# FlightPCB.net
KiCad netlist of a schematic drawn in EAGLE
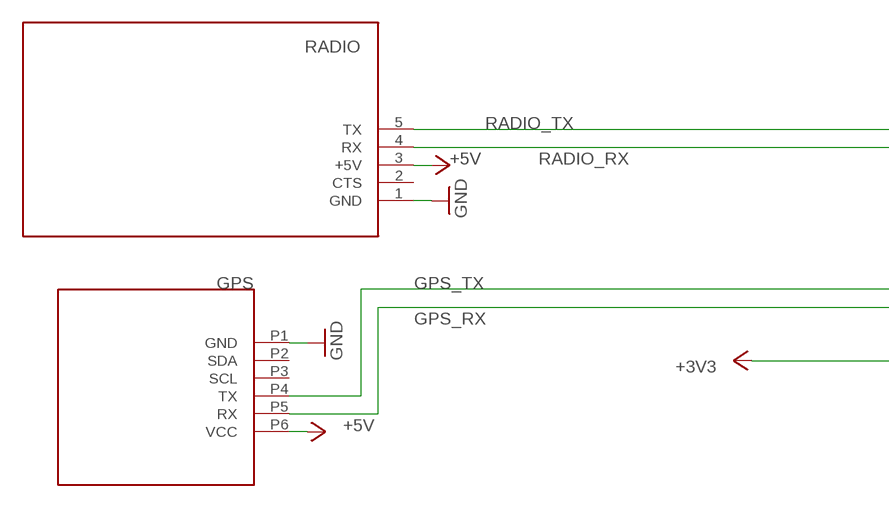
[diagram p0: schematic, sheet 1, part 1 of 2]
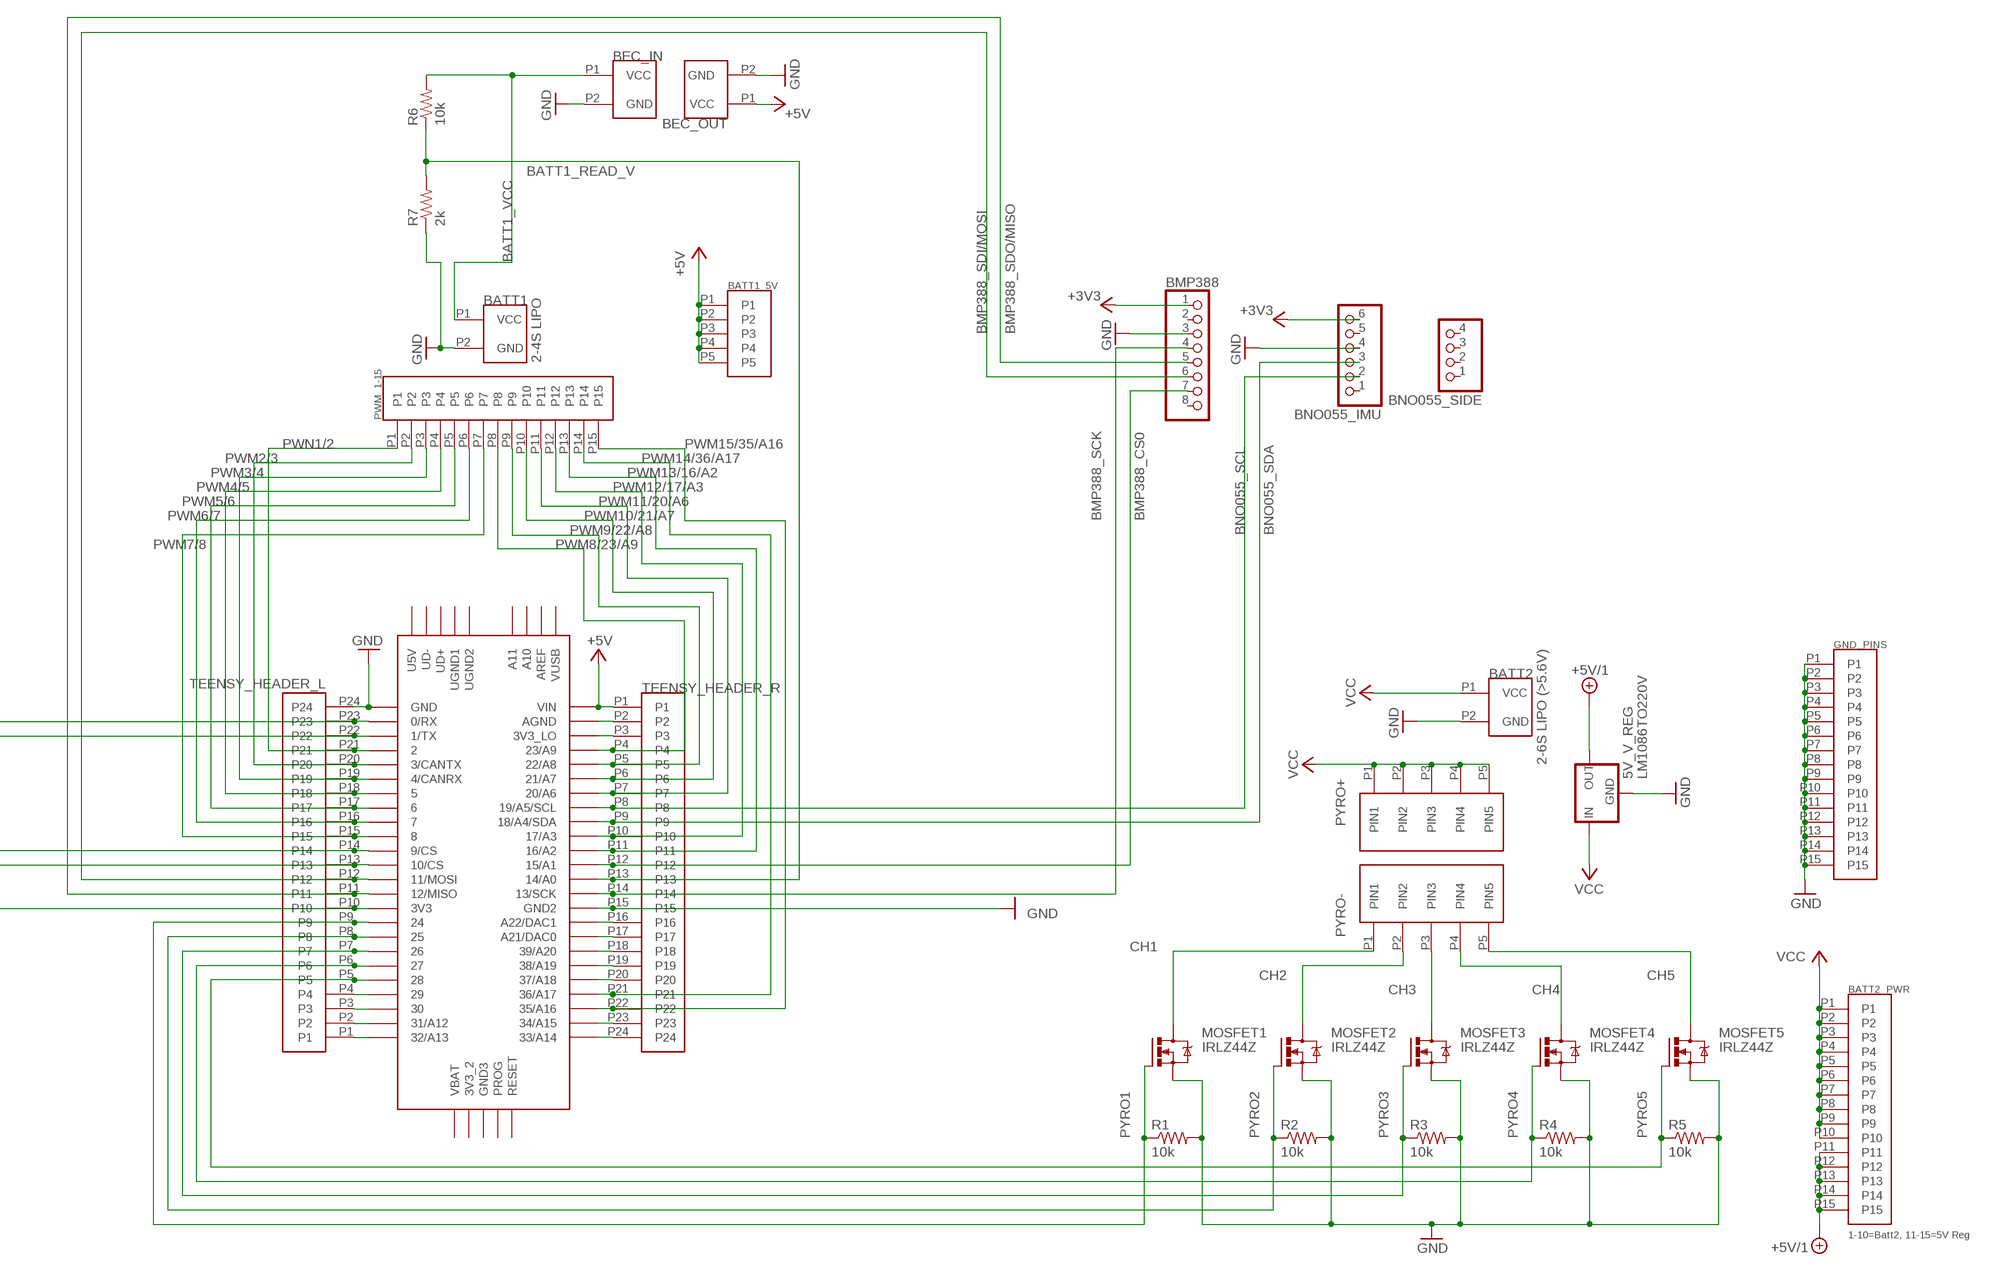
[diagram p1: schematic, sheet 1, part 2 of 2]

(export (version "E")
  (design (tool "Eeschema 10.0.6"))
  (components
    (comp (ref "5V_V_REG")
      (value "LM1086TO220V")
      (footprint "eagle-import:TO220S")
      (libsource (lib "eagle-import") (part "LM1086TO220V"))
    )
    (comp (ref "BATT1")
      (value "2-4S LIPO")
      (footprint "eagle-import:TERMINAL_BLOCK_2_PIN_5MM")
      (libsource (lib "eagle-import") (part "TERMINAL_BLOCK_2_PIN_5MM"))
    )
    (comp (ref "BATT1_5V")
      (value "PIN_HEADER_5")
      (footprint "eagle-import:PIN_HEADER_5")
      (libsource (lib "eagle-import") (part "PIN_HEADER_5"))
    )
    (comp (ref "BATT2")
      (value "2-6S LIPO (>5.6V)")
      (footprint "eagle-import:TERMINAL_BLOCK_2_PIN_5MM")
      (libsource (lib "eagle-import") (part "TERMINAL_BLOCK_2_PIN_5MM"))
    )
    (comp (ref "BATT2_PWR")
      (value "1-10=Batt2, 11-15=5V Reg")
      (footprint "eagle-import:PIN_HEADER_15")
      (libsource (lib "eagle-import") (part "PIN_HEADER_15"))
    )
    (comp (ref "BEC_IN")
      (value "TERMINAL_BLOCK_2_PIN_5MM")
      (footprint "eagle-import:TERMINAL_BLOCK_2_PIN_5MM")
      (libsource (lib "eagle-import") (part "TERMINAL_BLOCK_2_PIN_5MM"))
    )
    (comp (ref "BEC_OUT")
      (value "TERMINAL_BLOCK_2_PIN_5MM")
      (footprint "eagle-import:TERMINAL_BLOCK_2_PIN_5MM")
      (libsource (lib "eagle-import") (part "TERMINAL_BLOCK_2_PIN_5MM"))
    )
    (comp (ref "BMP388")
      (value "MICROBUILDER_HEADER-1X8ROUND")
      (footprint "eagle-import:MICROBUILDER_1X08_ROUND")
      (libsource (lib "eagle-import") (part "MICROBUILDER_HEADER-1X8ROUND"))
    )
    (comp (ref "BNO055_IMU")
      (value "MICROBUILDER_HEADER-1X6ROUND")
      (footprint "eagle-import:MICROBUILDER_1X06_ROUND")
      (libsource (lib "eagle-import") (part "MICROBUILDER_HEADER-1X6ROUND"))
    )
    (comp (ref "BNO055_SIDE")
      (value "MICROBUILDER_HEADER-1X4ROUND")
      (footprint "eagle-import:MICROBUILDER_1X04_ROUND")
      (libsource (lib "eagle-import") (part "MICROBUILDER_HEADER-1X4ROUND"))
    )
    (comp (ref "FLIGHT_COMPUTER")
      (value "TEENSY_3.5/3.6")
      (footprint "eagle-import:TEENSY_3.5_3.6")
      (libsource (lib "eagle-import") (part "TEENSY_3.5/3.6"))
    )
    (comp (ref "GND_PINS")
      (value "PIN_HEADER_15")
      (footprint "eagle-import:PIN_HEADER_15")
      (libsource (lib "eagle-import") (part "PIN_HEADER_15"))
    )
    (comp (ref "GPS")
      (value "NEO_M8N_GPS_BREAKOUT")
      (footprint "eagle-import:NEO_M8N_GPS_BREAKOUT")
      (libsource (lib "eagle-import") (part "NEO_M8N_GPS_BREAKOUT"))
    )
    (comp (ref "MOSFET1")
      (value "IRLZ44Z")
      (footprint "eagle-import:TO220BH_SIMPLE")
      (libsource (lib "eagle-import") (part "IRLZ44Z"))
    )
    (comp (ref "MOSFET2")
      (value "IRLZ44Z")
      (footprint "eagle-import:TO220BH_SIMPLE")
      (libsource (lib "eagle-import") (part "IRLZ44Z"))
    )
    (comp (ref "MOSFET3")
      (value "IRLZ44Z")
      (footprint "eagle-import:TO220BH_SIMPLE")
      (libsource (lib "eagle-import") (part "IRLZ44Z"))
    )
    (comp (ref "MOSFET4")
      (value "IRLZ44Z")
      (footprint "eagle-import:TO220BH_SIMPLE")
      (libsource (lib "eagle-import") (part "IRLZ44Z"))
    )
    (comp (ref "MOSFET5")
      (value "IRLZ44Z")
      (footprint "eagle-import:TO220BH_SIMPLE")
      (libsource (lib "eagle-import") (part "IRLZ44Z"))
    )
    (comp (ref "PWM_1-15")
      (value "PIN_HEADER_15")
      (footprint "eagle-import:PIN_HEADER_15")
      (libsource (lib "eagle-import") (part "PIN_HEADER_15"))
    )
    (comp (ref "PYRO+")
      (value "TERMINAL_BLOCK_5_PIN_5MM")
      (footprint "eagle-import:TERMINAL_BLOCK_5_PIN_5MM")
      (libsource (lib "eagle-import") (part "TERMINAL_BLOCK_5_PIN_5MM"))
    )
    (comp (ref "PYRO-")
      (value "TERMINAL_BLOCK_5_PIN_5MM")
      (footprint "eagle-import:TERMINAL_BLOCK_5_PIN_5MM")
      (libsource (lib "eagle-import") (part "TERMINAL_BLOCK_5_PIN_5MM"))
    )
    (comp (ref "R1")
      (value "10k")
      (footprint "eagle-import:0204_7")
      (libsource (lib "eagle-import") (part "R-US_0204/7"))
    )
    (comp (ref "R2")
      (value "10k")
      (footprint "eagle-import:0204_7")
      (libsource (lib "eagle-import") (part "R-US_0204/7"))
    )
    (comp (ref "R3")
      (value "10k")
      (footprint "eagle-import:0204_7")
      (libsource (lib "eagle-import") (part "R-US_0204/7"))
    )
    (comp (ref "R4")
      (value "10k")
      (footprint "eagle-import:0204_7")
      (libsource (lib "eagle-import") (part "R-US_0204/7"))
    )
    (comp (ref "R5")
      (value "10k")
      (footprint "eagle-import:0204_7")
      (libsource (lib "eagle-import") (part "R-US_0204/7"))
    )
    (comp (ref "R6")
      (value "10k")
      (footprint "eagle-import:0204_7")
      (libsource (lib "eagle-import") (part "R-US_0204/7"))
    )
    (comp (ref "R7")
      (value "2k")
      (footprint "eagle-import:0204_7")
      (libsource (lib "eagle-import") (part "R-US_0204/7"))
    )
    (comp (ref "RADIO")
      (value "RFD900")
      (footprint "eagle-import:RFD900")
      (libsource (lib "eagle-import") (part "RFD900"))
    )
    (comp (ref "TEENSY_HEADER_L")
      (value "PIN_HEADER_24_TEENSY_RAIL")
      (footprint "eagle-import:PIN_HEADER_24_TEENSY_RAIL")
      (libsource (lib "eagle-import") (part "PIN_HEADER_24_TEENSY_RAIL"))
    )
    (comp (ref "TEENSY_HEADER_R")
      (value "PIN_HEADER_24_TEENSY_RAIL")
      (footprint "eagle-import:PIN_HEADER_24_TEENSY_RAIL")
      (libsource (lib "eagle-import") (part "PIN_HEADER_24_TEENSY_RAIL"))
    )
  )
  (nets
    (net (code "1") (name "+3V3") (class "Default")
      (node (ref "BMP388") (pin "1") (pinfunction "1_1") (pintype "passive"))
      (node (ref "BNO055_IMU") (pin "6") (pinfunction "6_6") (pintype "passive"))
      (node (ref "FLIGHT_COMPUTER") (pin "3V3") (pinfunction "3V3_3V3") (pintype "bidirectional"))
      (node (ref "TEENSY_HEADER_L") (pin "P10") (pinfunction "P10_P10") (pintype "bidirectional"))
    )
    (net (code "2") (name "+5V") (class "Default")
      (node (ref "BATT1_5V") (pin "P1") (pinfunction "P1_P1") (pintype "bidirectional"))
      (node (ref "BATT1_5V") (pin "P2") (pinfunction "P2_P2") (pintype "bidirectional"))
      (node (ref "BATT1_5V") (pin "P3") (pinfunction "P3_P3") (pintype "bidirectional"))
      (node (ref "BATT1_5V") (pin "P4") (pinfunction "P4_P4") (pintype "bidirectional"))
      (node (ref "BATT1_5V") (pin "P5") (pinfunction "P5_P5") (pintype "bidirectional"))
      (node (ref "BEC_OUT") (pin "P1") (pinfunction "VCC_P1") (pintype "power_in"))
      (node (ref "FLIGHT_COMPUTER") (pin "VIN") (pinfunction "VIN_VIN") (pintype "bidirectional"))
      (node (ref "GPS") (pin "P6") (pinfunction "VCC_P6") (pintype "power_in"))
      (node (ref "RADIO") (pin "3") (pinfunction "+5V_3") (pintype "power_in"))
      (node (ref "TEENSY_HEADER_R") (pin "P1") (pinfunction "P1_P1") (pintype "bidirectional"))
    )
    (net (code "3") (name "+5V{slash}1") (class "Default")
      (node (ref "5V_V_REG") (pin "2") (pinfunction "OUT_2") (pintype "passive"))
      (node (ref "BATT2_PWR") (pin "P11") (pinfunction "P11_P11") (pintype "bidirectional"))
      (node (ref "BATT2_PWR") (pin "P12") (pinfunction "P12_P12") (pintype "bidirectional"))
      (node (ref "BATT2_PWR") (pin "P13") (pinfunction "P13_P13") (pintype "bidirectional"))
      (node (ref "BATT2_PWR") (pin "P14") (pinfunction "P14_P14") (pintype "bidirectional"))
      (node (ref "BATT2_PWR") (pin "P15") (pinfunction "P15_P15") (pintype "bidirectional"))
    )
    (net (code "4") (name "/BATT1_READ_V") (class "Default")
      (node (ref "FLIGHT_COMPUTER") (pin "14/A0") (pinfunction "14/A0_14/A0") (pintype "bidirectional"))
      (node (ref "R6") (pin "1") (pinfunction "1_1") (pintype "passive"))
      (node (ref "R7") (pin "2") (pinfunction "2_2") (pintype "passive"))
      (node (ref "TEENSY_HEADER_R") (pin "P13") (pinfunction "P13_P13") (pintype "bidirectional"))
    )
    (net (code "5") (name "/BATT1_VCC") (class "Default")
      (node (ref "BATT1") (pin "P1") (pinfunction "VCC_P1") (pintype "power_in"))
      (node (ref "BEC_IN") (pin "P1") (pinfunction "VCC_P1") (pintype "power_in"))
      (node (ref "R6") (pin "2") (pinfunction "2_2") (pintype "passive"))
    )
    (net (code "6") (name "/BMP388_CS0") (class "Default")
      (node (ref "BMP388") (pin "7") (pinfunction "7_7") (pintype "passive"))
      (node (ref "FLIGHT_COMPUTER") (pin "15/A1") (pinfunction "15/A1_15/A1") (pintype "bidirectional"))
      (node (ref "TEENSY_HEADER_R") (pin "P12") (pinfunction "P12_P12") (pintype "bidirectional"))
    )
    (net (code "7") (name "/BMP388_SCK") (class "Default")
      (node (ref "BMP388") (pin "4") (pinfunction "4_4") (pintype "passive"))
      (node (ref "FLIGHT_COMPUTER") (pin "13/SCK") (pinfunction "13/SCK_13/SCK") (pintype "bidirectional"))
      (node (ref "TEENSY_HEADER_R") (pin "P14") (pinfunction "P14_P14") (pintype "bidirectional"))
    )
    (net (code "8") (name "/BMP388_SDI{slash}MOSI") (class "Default")
      (node (ref "BMP388") (pin "6") (pinfunction "6_6") (pintype "passive"))
      (node (ref "FLIGHT_COMPUTER") (pin "11/MOSI") (pinfunction "11/MOSI_11/MOSI") (pintype "bidirectional"))
      (node (ref "TEENSY_HEADER_L") (pin "P12") (pinfunction "P12_P12") (pintype "bidirectional"))
    )
    (net (code "9") (name "/BMP388_SDO{slash}MISO") (class "Default")
      (node (ref "BMP388") (pin "5") (pinfunction "5_5") (pintype "passive"))
      (node (ref "FLIGHT_COMPUTER") (pin "12/MISO") (pinfunction "12/MISO_12/MISO") (pintype "bidirectional"))
      (node (ref "TEENSY_HEADER_L") (pin "P11") (pinfunction "P11_P11") (pintype "bidirectional"))
    )
    (net (code "10") (name "/BNO055_SCL") (class "Default")
      (node (ref "BNO055_IMU") (pin "2") (pinfunction "2_2") (pintype "passive"))
      (node (ref "FLIGHT_COMPUTER") (pin "19/A5/SCL") (pinfunction "19/A5/SCL_19/A5/SCL") (pintype "bidirectional"))
      (node (ref "TEENSY_HEADER_R") (pin "P8") (pinfunction "P8_P8") (pintype "bidirectional"))
    )
    (net (code "11") (name "/BNO055_SDA") (class "Default")
      (node (ref "BNO055_IMU") (pin "3") (pinfunction "3_3") (pintype "passive"))
      (node (ref "FLIGHT_COMPUTER") (pin "18/A4/SDA") (pinfunction "18/A4/SDA_18/A4/SDA") (pintype "bidirectional"))
      (node (ref "TEENSY_HEADER_R") (pin "P9") (pinfunction "P9_P9") (pintype "bidirectional"))
    )
    (net (code "12") (name "/CH1") (class "Default")
      (node (ref "MOSFET1") (pin "D") (pinfunction "D_D") (pintype "passive"))
      (node (ref "PYRO-") (pin "P1") (pinfunction "PIN1_P1") (pintype "bidirectional"))
    )
    (net (code "13") (name "/CH2") (class "Default")
      (node (ref "MOSFET2") (pin "D") (pinfunction "D_D") (pintype "passive"))
      (node (ref "PYRO-") (pin "P2") (pinfunction "PIN2_P2") (pintype "bidirectional"))
    )
    (net (code "14") (name "/CH3") (class "Default")
      (node (ref "MOSFET3") (pin "D") (pinfunction "D_D") (pintype "passive"))
      (node (ref "PYRO-") (pin "P3") (pinfunction "PIN3_P3") (pintype "bidirectional"))
    )
    (net (code "15") (name "/CH4") (class "Default")
      (node (ref "MOSFET4") (pin "D") (pinfunction "D_D") (pintype "passive"))
      (node (ref "PYRO-") (pin "P4") (pinfunction "PIN4_P4") (pintype "bidirectional"))
    )
    (net (code "16") (name "/CH5") (class "Default")
      (node (ref "MOSFET5") (pin "D") (pinfunction "D_D") (pintype "passive"))
      (node (ref "PYRO-") (pin "P5") (pinfunction "PIN5_P5") (pintype "bidirectional"))
    )
    (net (code "17") (name "/GPS_RX") (class "Default")
      (node (ref "FLIGHT_COMPUTER") (pin "10/CS") (pinfunction "10/CS_10/CS") (pintype "bidirectional"))
      (node (ref "GPS") (pin "P5") (pinfunction "RX_P5") (pintype "input"))
      (node (ref "TEENSY_HEADER_L") (pin "P13") (pinfunction "P13_P13") (pintype "bidirectional"))
    )
    (net (code "18") (name "/GPS_TX") (class "Default")
      (node (ref "FLIGHT_COMPUTER") (pin "9/CS") (pinfunction "9/CS_9/CS") (pintype "bidirectional"))
      (node (ref "GPS") (pin "P4") (pinfunction "TX_P4") (pintype "output"))
      (node (ref "TEENSY_HEADER_L") (pin "P14") (pinfunction "P14_P14") (pintype "bidirectional"))
    )
    (net (code "19") (name "/PWM2{slash}3") (class "Default")
      (node (ref "FLIGHT_COMPUTER") (pin "3/CANTX") (pinfunction "3/CANTX_3/CANTX") (pintype "bidirectional"))
      (node (ref "PWM_1-15") (pin "P2") (pinfunction "P2_P2") (pintype "bidirectional"))
      (node (ref "TEENSY_HEADER_L") (pin "P20") (pinfunction "P20_P20") (pintype "bidirectional"))
    )
    (net (code "20") (name "/PWM3{slash}4") (class "Default")
      (node (ref "FLIGHT_COMPUTER") (pin "4/CANRX") (pinfunction "4/CANRX_4/CANRX") (pintype "bidirectional"))
      (node (ref "PWM_1-15") (pin "P3") (pinfunction "P3_P3") (pintype "bidirectional"))
      (node (ref "TEENSY_HEADER_L") (pin "P19") (pinfunction "P19_P19") (pintype "bidirectional"))
    )
    (net (code "21") (name "/PWM4{slash}5") (class "Default")
      (node (ref "FLIGHT_COMPUTER") (pin "5") (pinfunction "5_5") (pintype "bidirectional"))
      (node (ref "PWM_1-15") (pin "P4") (pinfunction "P4_P4") (pintype "bidirectional"))
      (node (ref "TEENSY_HEADER_L") (pin "P18") (pinfunction "P18_P18") (pintype "bidirectional"))
    )
    (net (code "22") (name "/PWM5{slash}6") (class "Default")
      (node (ref "FLIGHT_COMPUTER") (pin "6") (pinfunction "6_6") (pintype "bidirectional"))
      (node (ref "PWM_1-15") (pin "P5") (pinfunction "P5_P5") (pintype "bidirectional"))
      (node (ref "TEENSY_HEADER_L") (pin "P17") (pinfunction "P17_P17") (pintype "bidirectional"))
    )
    (net (code "23") (name "/PWM6{slash}7") (class "Default")
      (node (ref "FLIGHT_COMPUTER") (pin "7") (pinfunction "7_7") (pintype "bidirectional"))
      (node (ref "PWM_1-15") (pin "P6") (pinfunction "P6_P6") (pintype "bidirectional"))
      (node (ref "TEENSY_HEADER_L") (pin "P16") (pinfunction "P16_P16") (pintype "bidirectional"))
    )
    (net (code "24") (name "/PWM7{slash}8") (class "Default")
      (node (ref "FLIGHT_COMPUTER") (pin "8") (pinfunction "8_8") (pintype "bidirectional"))
      (node (ref "PWM_1-15") (pin "P7") (pinfunction "P7_P7") (pintype "bidirectional"))
      (node (ref "TEENSY_HEADER_L") (pin "P15") (pinfunction "P15_P15") (pintype "bidirectional"))
    )
    (net (code "25") (name "/PWM8{slash}23{slash}A9") (class "Default")
      (node (ref "FLIGHT_COMPUTER") (pin "23/A9") (pinfunction "23/A9_23/A9") (pintype "bidirectional"))
      (node (ref "PWM_1-15") (pin "P8") (pinfunction "P8_P8") (pintype "bidirectional"))
      (node (ref "TEENSY_HEADER_R") (pin "P4") (pinfunction "P4_P4") (pintype "bidirectional"))
    )
    (net (code "26") (name "/PWM9{slash}22{slash}A8") (class "Default")
      (node (ref "FLIGHT_COMPUTER") (pin "22/A8") (pinfunction "22/A8_22/A8") (pintype "bidirectional"))
      (node (ref "PWM_1-15") (pin "P9") (pinfunction "P9_P9") (pintype "bidirectional"))
      (node (ref "TEENSY_HEADER_R") (pin "P5") (pinfunction "P5_P5") (pintype "bidirectional"))
    )
    (net (code "27") (name "/PWM10{slash}21{slash}A7") (class "Default")
      (node (ref "FLIGHT_COMPUTER") (pin "21/A7") (pinfunction "21/A7_21/A7") (pintype "bidirectional"))
      (node (ref "PWM_1-15") (pin "P10") (pinfunction "P10_P10") (pintype "bidirectional"))
      (node (ref "TEENSY_HEADER_R") (pin "P6") (pinfunction "P6_P6") (pintype "bidirectional"))
    )
    (net (code "28") (name "/PWM11{slash}20{slash}A6") (class "Default")
      (node (ref "FLIGHT_COMPUTER") (pin "20/A6") (pinfunction "20/A6_20/A6") (pintype "bidirectional"))
      (node (ref "PWM_1-15") (pin "P11") (pinfunction "P11_P11") (pintype "bidirectional"))
      (node (ref "TEENSY_HEADER_R") (pin "P7") (pinfunction "P7_P7") (pintype "bidirectional"))
    )
    (net (code "29") (name "/PWM12{slash}17{slash}A3") (class "Default")
      (node (ref "FLIGHT_COMPUTER") (pin "17/A3") (pinfunction "17/A3_17/A3") (pintype "bidirectional"))
      (node (ref "PWM_1-15") (pin "P12") (pinfunction "P12_P12") (pintype "bidirectional"))
      (node (ref "TEENSY_HEADER_R") (pin "P10") (pinfunction "P10_P10") (pintype "bidirectional"))
    )
    (net (code "30") (name "/PWM13{slash}16{slash}A2") (class "Default")
      (node (ref "FLIGHT_COMPUTER") (pin "16/A2") (pinfunction "16/A2_16/A2") (pintype "bidirectional"))
      (node (ref "PWM_1-15") (pin "P13") (pinfunction "P13_P13") (pintype "bidirectional"))
      (node (ref "TEENSY_HEADER_R") (pin "P11") (pinfunction "P11_P11") (pintype "bidirectional"))
    )
    (net (code "31") (name "/PWM14{slash}36{slash}A17") (class "Default")
      (node (ref "FLIGHT_COMPUTER") (pin "36/A17") (pinfunction "36/A17_36/A17") (pintype "bidirectional"))
      (node (ref "PWM_1-15") (pin "P14") (pinfunction "P14_P14") (pintype "bidirectional"))
      (node (ref "TEENSY_HEADER_R") (pin "P21") (pinfunction "P21_P21") (pintype "bidirectional"))
    )
    (net (code "32") (name "/PWM15{slash}35{slash}A16") (class "Default")
      (node (ref "FLIGHT_COMPUTER") (pin "35/A16") (pinfunction "35/A16_35/A16") (pintype "bidirectional"))
      (node (ref "PWM_1-15") (pin "P15") (pinfunction "P15_P15") (pintype "bidirectional"))
      (node (ref "TEENSY_HEADER_R") (pin "P22") (pinfunction "P22_P22") (pintype "bidirectional"))
    )
    (net (code "33") (name "/PWN1{slash}2") (class "Default")
      (node (ref "FLIGHT_COMPUTER") (pin "2") (pinfunction "2_2") (pintype "bidirectional"))
      (node (ref "PWM_1-15") (pin "P1") (pinfunction "P1_P1") (pintype "bidirectional"))
      (node (ref "TEENSY_HEADER_L") (pin "P21") (pinfunction "P21_P21") (pintype "bidirectional"))
    )
    (net (code "34") (name "/PYRO1") (class "Default")
      (node (ref "FLIGHT_COMPUTER") (pin "24") (pinfunction "24_24") (pintype "bidirectional"))
      (node (ref "MOSFET1") (pin "G") (pinfunction "G_G") (pintype "passive"))
      (node (ref "R1") (pin "1") (pinfunction "1_1") (pintype "passive"))
      (node (ref "TEENSY_HEADER_L") (pin "P9") (pinfunction "P9_P9") (pintype "bidirectional"))
    )
    (net (code "35") (name "/PYRO2") (class "Default")
      (node (ref "FLIGHT_COMPUTER") (pin "25") (pinfunction "25_25") (pintype "bidirectional"))
      (node (ref "MOSFET2") (pin "G") (pinfunction "G_G") (pintype "passive"))
      (node (ref "R2") (pin "1") (pinfunction "1_1") (pintype "passive"))
      (node (ref "TEENSY_HEADER_L") (pin "P8") (pinfunction "P8_P8") (pintype "bidirectional"))
    )
    (net (code "36") (name "/PYRO3") (class "Default")
      (node (ref "FLIGHT_COMPUTER") (pin "26") (pinfunction "26_26") (pintype "bidirectional"))
      (node (ref "MOSFET3") (pin "G") (pinfunction "G_G") (pintype "passive"))
      (node (ref "R3") (pin "1") (pinfunction "1_1") (pintype "passive"))
      (node (ref "TEENSY_HEADER_L") (pin "P7") (pinfunction "P7_P7") (pintype "bidirectional"))
    )
    (net (code "37") (name "/PYRO4") (class "Default")
      (node (ref "FLIGHT_COMPUTER") (pin "27") (pinfunction "27_27") (pintype "bidirectional"))
      (node (ref "MOSFET4") (pin "G") (pinfunction "G_G") (pintype "passive"))
      (node (ref "R4") (pin "1") (pinfunction "1_1") (pintype "passive"))
      (node (ref "TEENSY_HEADER_L") (pin "P6") (pinfunction "P6_P6") (pintype "bidirectional"))
    )
    (net (code "38") (name "/PYRO5") (class "Default")
      (node (ref "FLIGHT_COMPUTER") (pin "28") (pinfunction "28_28") (pintype "bidirectional"))
      (node (ref "MOSFET5") (pin "G") (pinfunction "G_G") (pintype "passive"))
      (node (ref "R5") (pin "1") (pinfunction "1_1") (pintype "passive"))
      (node (ref "TEENSY_HEADER_L") (pin "P5") (pinfunction "P5_P5") (pintype "bidirectional"))
    )
    (net (code "39") (name "/RADIO_RX") (class "Default")
      (node (ref "FLIGHT_COMPUTER") (pin "1/TX") (pinfunction "1/TX_1/TX") (pintype "bidirectional"))
      (node (ref "RADIO") (pin "4") (pinfunction "RX_4") (pintype "input"))
      (node (ref "TEENSY_HEADER_L") (pin "P22") (pinfunction "P22_P22") (pintype "bidirectional"))
    )
    (net (code "40") (name "/RADIO_TX") (class "Default")
      (node (ref "FLIGHT_COMPUTER") (pin "0/RX") (pinfunction "0/RX_0/RX") (pintype "bidirectional"))
      (node (ref "RADIO") (pin "5") (pinfunction "TX_5") (pintype "output"))
      (node (ref "TEENSY_HEADER_L") (pin "P23") (pinfunction "P23_P23") (pintype "bidirectional"))
    )
    (net (code "41") (name "GND") (class "Default")
      (node (ref "5V_V_REG") (pin "1") (pinfunction "GND_1") (pintype "input"))
      (node (ref "BATT1") (pin "P2") (pinfunction "GND_P2") (pintype "power_in"))
      (node (ref "BATT2") (pin "P2") (pinfunction "GND_P2") (pintype "power_in"))
      (node (ref "BEC_IN") (pin "P2") (pinfunction "GND_P2") (pintype "power_in"))
      (node (ref "BEC_OUT") (pin "P2") (pinfunction "GND_P2") (pintype "power_in"))
      (node (ref "BMP388") (pin "3") (pinfunction "3_3") (pintype "passive"))
      (node (ref "BNO055_IMU") (pin "4") (pinfunction "4_4") (pintype "passive"))
      (node (ref "FLIGHT_COMPUTER") (pin "GND") (pinfunction "GND_GND") (pintype "bidirectional"))
      (node (ref "FLIGHT_COMPUTER") (pin "GND2") (pinfunction "GND2_GND2") (pintype "bidirectional"))
      (node (ref "GND_PINS") (pin "P1") (pinfunction "P1_P1") (pintype "bidirectional"))
      (node (ref "GND_PINS") (pin "P10") (pinfunction "P10_P10") (pintype "bidirectional"))
      (node (ref "GND_PINS") (pin "P11") (pinfunction "P11_P11") (pintype "bidirectional"))
      (node (ref "GND_PINS") (pin "P12") (pinfunction "P12_P12") (pintype "bidirectional"))
      (node (ref "GND_PINS") (pin "P13") (pinfunction "P13_P13") (pintype "bidirectional"))
      (node (ref "GND_PINS") (pin "P14") (pinfunction "P14_P14") (pintype "bidirectional"))
      (node (ref "GND_PINS") (pin "P15") (pinfunction "P15_P15") (pintype "bidirectional"))
      (node (ref "GND_PINS") (pin "P2") (pinfunction "P2_P2") (pintype "bidirectional"))
      (node (ref "GND_PINS") (pin "P3") (pinfunction "P3_P3") (pintype "bidirectional"))
      (node (ref "GND_PINS") (pin "P4") (pinfunction "P4_P4") (pintype "bidirectional"))
      (node (ref "GND_PINS") (pin "P5") (pinfunction "P5_P5") (pintype "bidirectional"))
      (node (ref "GND_PINS") (pin "P6") (pinfunction "P6_P6") (pintype "bidirectional"))
      (node (ref "GND_PINS") (pin "P7") (pinfunction "P7_P7") (pintype "bidirectional"))
      (node (ref "GND_PINS") (pin "P8") (pinfunction "P8_P8") (pintype "bidirectional"))
      (node (ref "GND_PINS") (pin "P9") (pinfunction "P9_P9") (pintype "bidirectional"))
      (node (ref "GPS") (pin "P1") (pinfunction "GND_P1") (pintype "power_in"))
      (node (ref "MOSFET1") (pin "S") (pinfunction "S_S") (pintype "passive"))
      (node (ref "MOSFET2") (pin "S") (pinfunction "S_S") (pintype "passive"))
      (node (ref "MOSFET3") (pin "S") (pinfunction "S_S") (pintype "passive"))
      (node (ref "MOSFET4") (pin "S") (pinfunction "S_S") (pintype "passive"))
      (node (ref "MOSFET5") (pin "S") (pinfunction "S_S") (pintype "passive"))
      (node (ref "R1") (pin "2") (pinfunction "2_2") (pintype "passive"))
      (node (ref "R2") (pin "2") (pinfunction "2_2") (pintype "passive"))
      (node (ref "R3") (pin "2") (pinfunction "2_2") (pintype "passive"))
      (node (ref "R4") (pin "2") (pinfunction "2_2") (pintype "passive"))
      (node (ref "R5") (pin "2") (pinfunction "2_2") (pintype "passive"))
      (node (ref "R7") (pin "1") (pinfunction "1_1") (pintype "passive"))
      (node (ref "RADIO") (pin "1") (pinfunction "GND_1") (pintype "power_in"))
      (node (ref "TEENSY_HEADER_L") (pin "P24") (pinfunction "P24_P24") (pintype "bidirectional"))
      (node (ref "TEENSY_HEADER_R") (pin "P15") (pinfunction "P15_P15") (pintype "bidirectional"))
    )
    (net (code "42") (name "Net-(FLIGHT_COMPUTER-A21{slash}DAC0)") (class "Default")
      (node (ref "FLIGHT_COMPUTER") (pin "21/DAC0") (pinfunction "A21/DAC0_21/DAC0") (pintype "bidirectional"))
      (node (ref "TEENSY_HEADER_R") (pin "P17") (pinfunction "P17_P17") (pintype "bidirectional"))
    )
    (net (code "43") (name "Net-(FLIGHT_COMPUTER-Pad3V3_LO)") (class "Default")
      (node (ref "FLIGHT_COMPUTER") (pin "3V3_LO") (pinfunction "3V3_LO_3V3_LO") (pintype "bidirectional"))
      (node (ref "TEENSY_HEADER_R") (pin "P3") (pinfunction "P3_P3") (pintype "bidirectional"))
    )
    (net (code "44") (name "Net-(FLIGHT_COMPUTER-Pad29)") (class "Default")
      (node (ref "FLIGHT_COMPUTER") (pin "29") (pinfunction "29_29") (pintype "bidirectional"))
      (node (ref "TEENSY_HEADER_L") (pin "P4") (pinfunction "P4_P4") (pintype "bidirectional"))
    )
    (net (code "45") (name "Net-(FLIGHT_COMPUTER-Pad30)") (class "Default")
      (node (ref "FLIGHT_COMPUTER") (pin "30") (pinfunction "30_30") (pintype "bidirectional"))
      (node (ref "TEENSY_HEADER_L") (pin "P3") (pinfunction "P3_P3") (pintype "bidirectional"))
    )
    (net (code "46") (name "Net-(FLIGHT_COMPUTER-Pad31{slash}A12)") (class "Default")
      (node (ref "FLIGHT_COMPUTER") (pin "31/A12") (pinfunction "31/A12_31/A12") (pintype "bidirectional"))
      (node (ref "TEENSY_HEADER_L") (pin "P2") (pinfunction "P2_P2") (pintype "bidirectional"))
    )
    (net (code "47") (name "Net-(FLIGHT_COMPUTER-Pad32{slash}A13)") (class "Default")
      (node (ref "FLIGHT_COMPUTER") (pin "32/A13") (pinfunction "32/A13_32/A13") (pintype "bidirectional"))
      (node (ref "TEENSY_HEADER_L") (pin "P1") (pinfunction "P1_P1") (pintype "bidirectional"))
    )
    (net (code "48") (name "Net-(FLIGHT_COMPUTER-Pad33{slash}A14)") (class "Default")
      (node (ref "FLIGHT_COMPUTER") (pin "33/A14") (pinfunction "33/A14_33/A14") (pintype "bidirectional"))
      (node (ref "TEENSY_HEADER_R") (pin "P24") (pinfunction "P24_P24") (pintype "bidirectional"))
    )
    (net (code "49") (name "Net-(FLIGHT_COMPUTER-Pad34{slash}A15)") (class "Default")
      (node (ref "FLIGHT_COMPUTER") (pin "34/A15") (pinfunction "34/A15_34/A15") (pintype "bidirectional"))
      (node (ref "TEENSY_HEADER_R") (pin "P23") (pinfunction "P23_P23") (pintype "bidirectional"))
    )
    (net (code "50") (name "Net-(FLIGHT_COMPUTER-Pad37{slash}A18)") (class "Default")
      (node (ref "FLIGHT_COMPUTER") (pin "37/A18") (pinfunction "37/A18_37/A18") (pintype "bidirectional"))
      (node (ref "TEENSY_HEADER_R") (pin "P20") (pinfunction "P20_P20") (pintype "bidirectional"))
    )
    (net (code "51") (name "Net-(FLIGHT_COMPUTER-Pad38{slash}A19)") (class "Default")
      (node (ref "FLIGHT_COMPUTER") (pin "38/A19") (pinfunction "38/A19_38/A19") (pintype "bidirectional"))
      (node (ref "TEENSY_HEADER_R") (pin "P19") (pinfunction "P19_P19") (pintype "bidirectional"))
    )
    (net (code "52") (name "Net-(FLIGHT_COMPUTER-Pad39{slash}A20)") (class "Default")
      (node (ref "FLIGHT_COMPUTER") (pin "39/A20") (pinfunction "39/A20_39/A20") (pintype "bidirectional"))
      (node (ref "TEENSY_HEADER_R") (pin "P18") (pinfunction "P18_P18") (pintype "bidirectional"))
    )
    (net (code "53") (name "Net-(FLIGHT_COMPUTER-PadA22{slash}DAC1)") (class "Default")
      (node (ref "FLIGHT_COMPUTER") (pin "A22/DAC1") (pinfunction "A22/DAC1_A22/DAC1") (pintype "bidirectional"))
      (node (ref "TEENSY_HEADER_R") (pin "P16") (pinfunction "P16_P16") (pintype "bidirectional"))
    )
    (net (code "54") (name "Net-(FLIGHT_COMPUTER-PadAGND)") (class "Default")
      (node (ref "FLIGHT_COMPUTER") (pin "AGND") (pinfunction "AGND_AGND") (pintype "bidirectional"))
      (node (ref "TEENSY_HEADER_R") (pin "P2") (pinfunction "P2_P2") (pintype "bidirectional"))
    )
    (net (code "55") (name "VCC") (class "Default")
      (node (ref "5V_V_REG") (pin "3") (pinfunction "IN_3") (pintype "input"))
      (node (ref "BATT2") (pin "P1") (pinfunction "VCC_P1") (pintype "power_in"))
      (node (ref "BATT2_PWR") (pin "P1") (pinfunction "P1_P1") (pintype "bidirectional"))
      (node (ref "BATT2_PWR") (pin "P10") (pinfunction "P10_P10") (pintype "bidirectional"))
      (node (ref "BATT2_PWR") (pin "P2") (pinfunction "P2_P2") (pintype "bidirectional"))
      (node (ref "BATT2_PWR") (pin "P3") (pinfunction "P3_P3") (pintype "bidirectional"))
      (node (ref "BATT2_PWR") (pin "P4") (pinfunction "P4_P4") (pintype "bidirectional"))
      (node (ref "BATT2_PWR") (pin "P5") (pinfunction "P5_P5") (pintype "bidirectional"))
      (node (ref "BATT2_PWR") (pin "P6") (pinfunction "P6_P6") (pintype "bidirectional"))
      (node (ref "BATT2_PWR") (pin "P7") (pinfunction "P7_P7") (pintype "bidirectional"))
      (node (ref "BATT2_PWR") (pin "P8") (pinfunction "P8_P8") (pintype "bidirectional"))
      (node (ref "BATT2_PWR") (pin "P9") (pinfunction "P9_P9") (pintype "bidirectional"))
      (node (ref "PYRO+") (pin "P1") (pinfunction "PIN1_P1") (pintype "bidirectional"))
      (node (ref "PYRO+") (pin "P2") (pinfunction "PIN2_P2") (pintype "bidirectional"))
      (node (ref "PYRO+") (pin "P3") (pinfunction "PIN3_P3") (pintype "bidirectional"))
      (node (ref "PYRO+") (pin "P4") (pinfunction "PIN4_P4") (pintype "bidirectional"))
      (node (ref "PYRO+") (pin "P5") (pinfunction "PIN5_P5") (pintype "bidirectional"))
    )
    (net (code "56") (name "unconnected-(BMP388-Pad2)") (class "Default")
      (node (ref "BMP388") (pin "2") (pinfunction "2_2") (pintype "passive"))
    )
    (net (code "57") (name "unconnected-(BMP388-Pad8)") (class "Default")
      (node (ref "BMP388") (pin "8") (pinfunction "8_8") (pintype "passive"))
    )
    (net (code "58") (name "unconnected-(BNO055_IMU-Pad1)") (class "Default")
      (node (ref "BNO055_IMU") (pin "1") (pinfunction "1_1") (pintype "passive"))
    )
    (net (code "59") (name "unconnected-(BNO055_IMU-Pad5)") (class "Default")
      (node (ref "BNO055_IMU") (pin "5") (pinfunction "5_5") (pintype "passive"))
    )
    (net (code "60") (name "unconnected-(BNO055_SIDE-Pad1)") (class "Default")
      (node (ref "BNO055_SIDE") (pin "1") (pinfunction "1_1") (pintype "passive"))
    )
    (net (code "61") (name "unconnected-(BNO055_SIDE-Pad2)") (class "Default")
      (node (ref "BNO055_SIDE") (pin "2") (pinfunction "2_2") (pintype "passive"))
    )
    (net (code "62") (name "unconnected-(BNO055_SIDE-Pad3)") (class "Default")
      (node (ref "BNO055_SIDE") (pin "3") (pinfunction "3_3") (pintype "passive"))
    )
    (net (code "63") (name "unconnected-(BNO055_SIDE-Pad4)") (class "Default")
      (node (ref "BNO055_SIDE") (pin "4") (pinfunction "4_4") (pintype "passive"))
    )
    (net (code "64") (name "unconnected-(FLIGHT_COMPUTER-Pad3V3_2)") (class "Default")
      (node (ref "FLIGHT_COMPUTER") (pin "3V3_2") (pinfunction "3V3_2_3V3_2") (pintype "bidirectional"))
    )
    (net (code "65") (name "unconnected-(FLIGHT_COMPUTER-PadA10)") (class "Default")
      (node (ref "FLIGHT_COMPUTER") (pin "A10") (pinfunction "A10_A10") (pintype "bidirectional"))
    )
    (net (code "66") (name "unconnected-(FLIGHT_COMPUTER-PadA11)") (class "Default")
      (node (ref "FLIGHT_COMPUTER") (pin "A11") (pinfunction "A11_A11") (pintype "bidirectional"))
    )
    (net (code "67") (name "unconnected-(FLIGHT_COMPUTER-PadAREF)") (class "Default")
      (node (ref "FLIGHT_COMPUTER") (pin "AREF") (pinfunction "AREF_AREF") (pintype "bidirectional"))
    )
    (net (code "68") (name "unconnected-(FLIGHT_COMPUTER-PadGND3)") (class "Default")
      (node (ref "FLIGHT_COMPUTER") (pin "GND3") (pinfunction "GND3_GND3") (pintype "bidirectional"))
    )
    (net (code "69") (name "unconnected-(FLIGHT_COMPUTER-PadPROG)") (class "Default")
      (node (ref "FLIGHT_COMPUTER") (pin "PROG") (pinfunction "PROG_PROG") (pintype "bidirectional"))
    )
    (net (code "70") (name "unconnected-(FLIGHT_COMPUTER-PadRESET)") (class "Default")
      (node (ref "FLIGHT_COMPUTER") (pin "RESET") (pinfunction "RESET_RESET") (pintype "bidirectional"))
    )
    (net (code "71") (name "unconnected-(FLIGHT_COMPUTER-PadU5V)") (class "Default")
      (node (ref "FLIGHT_COMPUTER") (pin "U5V") (pinfunction "U5V_U5V") (pintype "bidirectional"))
    )
    (net (code "72") (name "unconnected-(FLIGHT_COMPUTER-PadUD+)") (class "Default")
      (node (ref "FLIGHT_COMPUTER") (pin "UD+") (pinfunction "UD+_UD+") (pintype "bidirectional"))
    )
    (net (code "73") (name "unconnected-(FLIGHT_COMPUTER-PadUD-)") (class "Default")
      (node (ref "FLIGHT_COMPUTER") (pin "UD-") (pinfunction "UD-_UD-") (pintype "bidirectional"))
    )
    (net (code "74") (name "unconnected-(FLIGHT_COMPUTER-PadUGND1)") (class "Default")
      (node (ref "FLIGHT_COMPUTER") (pin "UGND1") (pinfunction "UGND1_UGND1") (pintype "bidirectional"))
    )
    (net (code "75") (name "unconnected-(FLIGHT_COMPUTER-PadUGND2)") (class "Default")
      (node (ref "FLIGHT_COMPUTER") (pin "UGND2") (pinfunction "UGND2_UGND2") (pintype "bidirectional"))
    )
    (net (code "76") (name "unconnected-(FLIGHT_COMPUTER-PadVBAT)") (class "Default")
      (node (ref "FLIGHT_COMPUTER") (pin "VBAT") (pinfunction "VBAT_VBAT") (pintype "bidirectional"))
    )
    (net (code "77") (name "unconnected-(FLIGHT_COMPUTER-PadVUSB)") (class "Default")
      (node (ref "FLIGHT_COMPUTER") (pin "VUSB") (pinfunction "VUSB_VUSB") (pintype "bidirectional"))
    )
    (net (code "78") (name "unconnected-(GPS-SCL-PadP3)") (class "Default")
      (node (ref "GPS") (pin "P3") (pinfunction "SCL_P3") (pintype "no_connect"))
    )
    (net (code "79") (name "unconnected-(GPS-SDA-PadP2)") (class "Default")
      (node (ref "GPS") (pin "P2") (pinfunction "SDA_P2") (pintype "no_connect"))
    )
    (net (code "80") (name "unconnected-(RADIO-CTS-Pad2)") (class "Default")
      (node (ref "RADIO") (pin "2") (pinfunction "CTS_2") (pintype "no_connect"))
    )
  )
)
